# equalizer_schematic.net
KiCad netlist of a schematic drawn in EAGLE
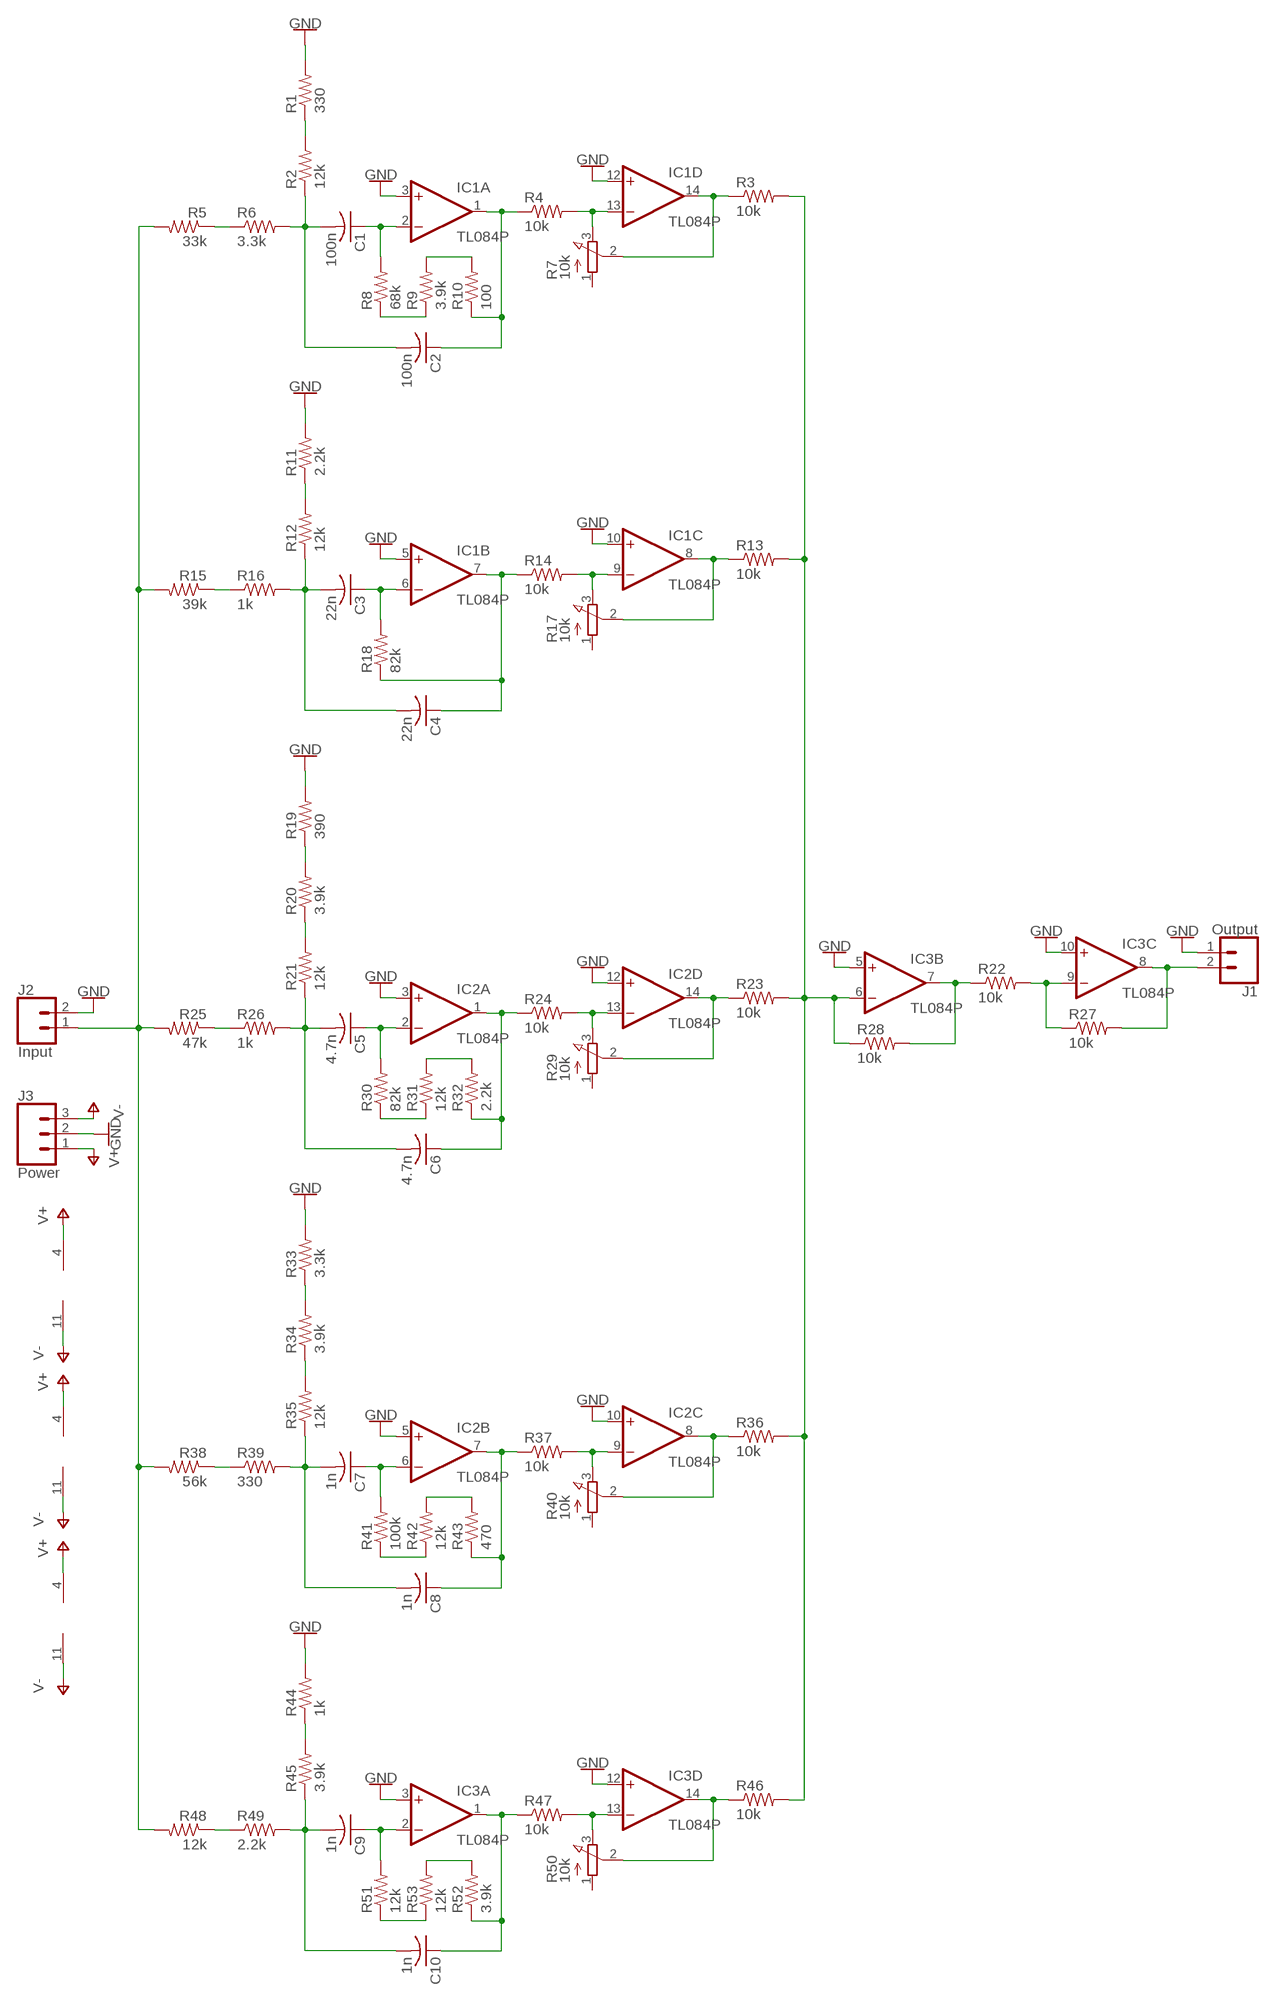
[diagram p0: schematic, sheet 1]

(export (version "E")
  (design (tool "Eeschema 10.0.6"))
  (components
    (comp (ref "C1")
      (value "100n")
      (footprint "eagle-import:C075-032X103")
      (libsource (lib "eagle-import") (part "C-US075-032X103"))
    )
    (comp (ref "C2")
      (value "100n")
      (footprint "eagle-import:C075-032X103")
      (libsource (lib "eagle-import") (part "C-US075-032X103"))
    )
    (comp (ref "C3")
      (value "22n")
      (footprint "eagle-import:C075-032X103")
      (libsource (lib "eagle-import") (part "C-US075-032X103"))
    )
    (comp (ref "C4")
      (value "22n")
      (footprint "eagle-import:C075-032X103")
      (libsource (lib "eagle-import") (part "C-US075-032X103"))
    )
    (comp (ref "C5")
      (value "4.7n")
      (footprint "eagle-import:C050-024X044")
      (libsource (lib "eagle-import") (part "C-US050-024X044"))
    )
    (comp (ref "C6")
      (value "4.7n")
      (footprint "eagle-import:C050-024X044")
      (libsource (lib "eagle-import") (part "C-US050-024X044"))
    )
    (comp (ref "C7")
      (value "1n")
      (footprint "eagle-import:C050-024X044")
      (libsource (lib "eagle-import") (part "C-US050-024X044"))
    )
    (comp (ref "C8")
      (value "1n")
      (footprint "eagle-import:C050-024X044")
      (libsource (lib "eagle-import") (part "C-US050-024X044"))
    )
    (comp (ref "C9")
      (value "1n")
      (footprint "eagle-import:C050-024X044")
      (libsource (lib "eagle-import") (part "C-US050-024X044"))
    )
    (comp (ref "C10")
      (value "1n")
      (footprint "eagle-import:C050-024X044")
      (libsource (lib "eagle-import") (part "C-US050-024X044"))
    )
    (comp (ref "IC1")
      (value "TL084P")
      (footprint "eagle-import:DIL14")
      (libsource (lib "eagle-import") (part "TL084P"))
    )
    (comp (ref "IC2")
      (value "TL084P")
      (footprint "eagle-import:DIL14")
      (libsource (lib "eagle-import") (part "TL084P"))
    )
    (comp (ref "IC3")
      (value "TL084P")
      (footprint "eagle-import:DIL14")
      (libsource (lib "eagle-import") (part "TL084P"))
    )
    (comp (ref "J1")
      (value "Output")
      (footprint "eagle-import:SCREWTERMINAL-5MM-2")
      (libsource (lib "eagle-import") (part "CONN_025MM"))
    )
    (comp (ref "J2")
      (value "Input")
      (footprint "eagle-import:SCREWTERMINAL-5MM-2")
      (libsource (lib "eagle-import") (part "CONN_025MM"))
    )
    (comp (ref "J3")
      (value "Power")
      (footprint "eagle-import:SCREWTERMINAL-5MM-3")
      (libsource (lib "eagle-import") (part "CONN_03-SCREW-5MM"))
    )
    (comp (ref "R1")
      (value "330")
      (footprint "eagle-import:0207_7")
      (libsource (lib "eagle-import") (part "R-US_0207/7"))
    )
    (comp (ref "R2")
      (value "12k")
      (footprint "eagle-import:0207_7")
      (libsource (lib "eagle-import") (part "R-US_0207/7"))
    )
    (comp (ref "R3")
      (value "10k")
      (footprint "eagle-import:0207_7")
      (libsource (lib "eagle-import") (part "R-US_0207/7"))
    )
    (comp (ref "R4")
      (value "10k")
      (footprint "eagle-import:0207_7")
      (libsource (lib "eagle-import") (part "R-US_0207/7"))
    )
    (comp (ref "R5")
      (value "33k")
      (footprint "eagle-import:0207_7")
      (libsource (lib "eagle-import") (part "R-US_0207/7"))
    )
    (comp (ref "R6")
      (value "3.3k")
      (footprint "eagle-import:0207_7")
      (libsource (lib "eagle-import") (part "R-US_0207/7"))
    )
    (comp (ref "R7")
      (value "10k")
      (footprint "eagle-import:3RP_1610N")
      (libsource (lib "eagle-import") (part "3RP/1610N"))
    )
    (comp (ref "R8")
      (value "68k")
      (footprint "eagle-import:0207_7")
      (libsource (lib "eagle-import") (part "R-US_0207/7"))
    )
    (comp (ref "R9")
      (value "3.9k")
      (footprint "eagle-import:0207_7")
      (libsource (lib "eagle-import") (part "R-US_0207/7"))
    )
    (comp (ref "R10")
      (value "100")
      (footprint "eagle-import:0207_7")
      (libsource (lib "eagle-import") (part "R-US_0207/7"))
    )
    (comp (ref "R11")
      (value "2.2k")
      (footprint "eagle-import:0207_7")
      (libsource (lib "eagle-import") (part "R-US_0207/7"))
    )
    (comp (ref "R12")
      (value "12k")
      (footprint "eagle-import:0207_7")
      (libsource (lib "eagle-import") (part "R-US_0207/7"))
    )
    (comp (ref "R13")
      (value "10k")
      (footprint "eagle-import:0207_7")
      (libsource (lib "eagle-import") (part "R-US_0207/7"))
    )
    (comp (ref "R14")
      (value "10k")
      (footprint "eagle-import:0207_7")
      (libsource (lib "eagle-import") (part "R-US_0207/7"))
    )
    (comp (ref "R15")
      (value "39k")
      (footprint "eagle-import:0207_7")
      (libsource (lib "eagle-import") (part "R-US_0207/7"))
    )
    (comp (ref "R16")
      (value "1k")
      (footprint "eagle-import:0207_7")
      (libsource (lib "eagle-import") (part "R-US_0207/7"))
    )
    (comp (ref "R17")
      (value "10k")
      (footprint "eagle-import:3RP_1610N")
      (libsource (lib "eagle-import") (part "3RP/1610N"))
    )
    (comp (ref "R18")
      (value "82k")
      (footprint "eagle-import:0207_7")
      (libsource (lib "eagle-import") (part "R-US_0207/7"))
    )
    (comp (ref "R19")
      (value "390")
      (footprint "eagle-import:0207_7")
      (libsource (lib "eagle-import") (part "R-US_0207/7"))
    )
    (comp (ref "R20")
      (value "3.9k")
      (footprint "eagle-import:0207_7")
      (libsource (lib "eagle-import") (part "R-US_0207/7"))
    )
    (comp (ref "R21")
      (value "12k")
      (footprint "eagle-import:0207_7")
      (libsource (lib "eagle-import") (part "R-US_0207/7"))
    )
    (comp (ref "R22")
      (value "10k")
      (footprint "eagle-import:0207_7")
      (libsource (lib "eagle-import") (part "R-US_0207/7"))
    )
    (comp (ref "R23")
      (value "10k")
      (footprint "eagle-import:0207_7")
      (libsource (lib "eagle-import") (part "R-US_0207/7"))
    )
    (comp (ref "R24")
      (value "10k")
      (footprint "eagle-import:0207_7")
      (libsource (lib "eagle-import") (part "R-US_0207/7"))
    )
    (comp (ref "R25")
      (value "47k")
      (footprint "eagle-import:0207_7")
      (libsource (lib "eagle-import") (part "R-US_0207/7"))
    )
    (comp (ref "R26")
      (value "1k")
      (footprint "eagle-import:0207_7")
      (libsource (lib "eagle-import") (part "R-US_0207/7"))
    )
    (comp (ref "R27")
      (value "10k")
      (footprint "eagle-import:0207_7")
      (libsource (lib "eagle-import") (part "R-US_0207/7"))
    )
    (comp (ref "R28")
      (value "10k")
      (footprint "eagle-import:0207_7")
      (libsource (lib "eagle-import") (part "R-US_0207/7"))
    )
    (comp (ref "R29")
      (value "10k")
      (footprint "eagle-import:3RP_1610N")
      (libsource (lib "eagle-import") (part "3RP/1610N"))
    )
    (comp (ref "R30")
      (value "82k")
      (footprint "eagle-import:0207_7")
      (libsource (lib "eagle-import") (part "R-US_0207/7"))
    )
    (comp (ref "R31")
      (value "12k")
      (footprint "eagle-import:0207_7")
      (libsource (lib "eagle-import") (part "R-US_0207/7"))
    )
    (comp (ref "R32")
      (value "2.2k")
      (footprint "eagle-import:0207_7")
      (libsource (lib "eagle-import") (part "R-US_0207/7"))
    )
    (comp (ref "R33")
      (value "3.3k")
      (footprint "eagle-import:0207_7")
      (libsource (lib "eagle-import") (part "R-US_0207/7"))
    )
    (comp (ref "R34")
      (value "3.9k")
      (footprint "eagle-import:0207_7")
      (libsource (lib "eagle-import") (part "R-US_0207/7"))
    )
    (comp (ref "R35")
      (value "12k")
      (footprint "eagle-import:0207_7")
      (libsource (lib "eagle-import") (part "R-US_0207/7"))
    )
    (comp (ref "R36")
      (value "10k")
      (footprint "eagle-import:0207_7")
      (libsource (lib "eagle-import") (part "R-US_0207/7"))
    )
    (comp (ref "R37")
      (value "10k")
      (footprint "eagle-import:0207_7")
      (libsource (lib "eagle-import") (part "R-US_0207/7"))
    )
    (comp (ref "R38")
      (value "56k")
      (footprint "eagle-import:0207_7")
      (libsource (lib "eagle-import") (part "R-US_0207/7"))
    )
    (comp (ref "R39")
      (value "330")
      (footprint "eagle-import:0207_7")
      (libsource (lib "eagle-import") (part "R-US_0207/7"))
    )
    (comp (ref "R40")
      (value "10k")
      (footprint "eagle-import:3RP_1610N")
      (libsource (lib "eagle-import") (part "3RP/1610N"))
    )
    (comp (ref "R41")
      (value "100k")
      (footprint "eagle-import:0207_7")
      (libsource (lib "eagle-import") (part "R-US_0207/7"))
    )
    (comp (ref "R42")
      (value "12k")
      (footprint "eagle-import:0207_7")
      (libsource (lib "eagle-import") (part "R-US_0207/7"))
    )
    (comp (ref "R43")
      (value "470")
      (footprint "eagle-import:0207_7")
      (libsource (lib "eagle-import") (part "R-US_0207/7"))
    )
    (comp (ref "R44")
      (value "1k")
      (footprint "eagle-import:0207_7")
      (libsource (lib "eagle-import") (part "R-US_0207/7"))
    )
    (comp (ref "R45")
      (value "3.9k")
      (footprint "eagle-import:0207_7")
      (libsource (lib "eagle-import") (part "R-US_0207/7"))
    )
    (comp (ref "R46")
      (value "10k")
      (footprint "eagle-import:0207_7")
      (libsource (lib "eagle-import") (part "R-US_0207/7"))
    )
    (comp (ref "R47")
      (value "10k")
      (footprint "eagle-import:0207_7")
      (libsource (lib "eagle-import") (part "R-US_0207/7"))
    )
    (comp (ref "R48")
      (value "12k")
      (footprint "eagle-import:0207_7")
      (libsource (lib "eagle-import") (part "R-US_0207/7"))
    )
    (comp (ref "R49")
      (value "2.2k")
      (footprint "eagle-import:0207_7")
      (libsource (lib "eagle-import") (part "R-US_0207/7"))
    )
    (comp (ref "R50")
      (value "10k")
      (footprint "eagle-import:3RP_1610N")
      (libsource (lib "eagle-import") (part "3RP/1610N"))
    )
    (comp (ref "R51")
      (value "12k")
      (footprint "eagle-import:0207_7")
      (libsource (lib "eagle-import") (part "R-US_0207/7"))
    )
    (comp (ref "R52")
      (value "3.9k")
      (footprint "eagle-import:0207_7")
      (libsource (lib "eagle-import") (part "R-US_0207/7"))
    )
    (comp (ref "R53")
      (value "12k")
      (footprint "eagle-import:0207_7")
      (libsource (lib "eagle-import") (part "R-US_0207/7"))
    )
  )
  (nets
    (net (code "1") (name "GND") (class "Default")
      (node (ref "IC1") (pin "10") (pinfunction "+IN_10") (pintype "input"))
      (node (ref "IC1") (pin "12") (pinfunction "+IN_12") (pintype "input"))
      (node (ref "IC1") (pin "3") (pinfunction "+IN_3") (pintype "input"))
      (node (ref "IC1") (pin "5") (pinfunction "+IN_5") (pintype "input"))
      (node (ref "IC2") (pin "10") (pinfunction "+IN_10") (pintype "input"))
      (node (ref "IC2") (pin "12") (pinfunction "+IN_12") (pintype "input"))
      (node (ref "IC2") (pin "3") (pinfunction "+IN_3") (pintype "input"))
      (node (ref "IC2") (pin "5") (pinfunction "+IN_5") (pintype "input"))
      (node (ref "IC3") (pin "10") (pinfunction "+IN_10") (pintype "input"))
      (node (ref "IC3") (pin "12") (pinfunction "+IN_12") (pintype "input"))
      (node (ref "IC3") (pin "3") (pinfunction "+IN_3") (pintype "input"))
      (node (ref "IC3") (pin "5") (pinfunction "+IN_5") (pintype "input"))
      (node (ref "J1") (pin "1") (pinfunction "1_1") (pintype "passive"))
      (node (ref "J2") (pin "2") (pinfunction "2_2") (pintype "passive"))
      (node (ref "J3") (pin "2") (pinfunction "2_2") (pintype "passive"))
      (node (ref "R1") (pin "2") (pinfunction "2_2") (pintype "passive"))
      (node (ref "R11") (pin "2") (pinfunction "2_2") (pintype "passive"))
      (node (ref "R19") (pin "2") (pinfunction "2_2") (pintype "passive"))
      (node (ref "R33") (pin "2") (pinfunction "2_2") (pintype "passive"))
      (node (ref "R44") (pin "2") (pinfunction "2_2") (pintype "passive"))
    )
    (net (code "2") (name "Net-(C1-Pad2)") (class "Default")
      (node (ref "C1") (pin "2") (pinfunction "2_2") (pintype "passive"))
      (node (ref "C2") (pin "2") (pinfunction "2_2") (pintype "passive"))
      (node (ref "R2") (pin "1") (pinfunction "1_1") (pintype "passive"))
      (node (ref "R6") (pin "2") (pinfunction "2_2") (pintype "passive"))
    )
    (net (code "3") (name "Net-(C3-Pad2)") (class "Default")
      (node (ref "C3") (pin "2") (pinfunction "2_2") (pintype "passive"))
      (node (ref "C4") (pin "2") (pinfunction "2_2") (pintype "passive"))
      (node (ref "R12") (pin "1") (pinfunction "1_1") (pintype "passive"))
      (node (ref "R16") (pin "2") (pinfunction "2_2") (pintype "passive"))
    )
    (net (code "4") (name "Net-(C5-Pad2)") (class "Default")
      (node (ref "C5") (pin "2") (pinfunction "2_2") (pintype "passive"))
      (node (ref "C6") (pin "2") (pinfunction "2_2") (pintype "passive"))
      (node (ref "R21") (pin "1") (pinfunction "1_1") (pintype "passive"))
      (node (ref "R26") (pin "2") (pinfunction "2_2") (pintype "passive"))
    )
    (net (code "5") (name "Net-(C7-Pad2)") (class "Default")
      (node (ref "C7") (pin "2") (pinfunction "2_2") (pintype "passive"))
      (node (ref "C8") (pin "2") (pinfunction "2_2") (pintype "passive"))
      (node (ref "R35") (pin "1") (pinfunction "1_1") (pintype "passive"))
      (node (ref "R39") (pin "2") (pinfunction "2_2") (pintype "passive"))
    )
    (net (code "6") (name "Net-(C10-Pad2)") (class "Default")
      (node (ref "C10") (pin "2") (pinfunction "2_2") (pintype "passive"))
      (node (ref "C9") (pin "2") (pinfunction "2_2") (pintype "passive"))
      (node (ref "R45") (pin "1") (pinfunction "1_1") (pintype "passive"))
      (node (ref "R49") (pin "2") (pinfunction "2_2") (pintype "passive"))
    )
    (net (code "7") (name "Net-(IC1A--IN)") (class "Default")
      (node (ref "C1") (pin "1") (pinfunction "1_1") (pintype "passive"))
      (node (ref "IC1") (pin "2") (pinfunction "-IN_2") (pintype "input"))
      (node (ref "R8") (pin "2") (pinfunction "2_2") (pintype "passive"))
    )
    (net (code "8") (name "Net-(IC1A-OUT)") (class "Default")
      (node (ref "C2") (pin "1") (pinfunction "1_1") (pintype "passive"))
      (node (ref "IC1") (pin "1") (pinfunction "OUT_1") (pintype "output"))
      (node (ref "R10") (pin "1") (pinfunction "1_1") (pintype "passive"))
      (node (ref "R4") (pin "1") (pinfunction "1_1") (pintype "passive"))
    )
    (net (code "9") (name "Net-(IC1B--IN)") (class "Default")
      (node (ref "C3") (pin "1") (pinfunction "1_1") (pintype "passive"))
      (node (ref "IC1") (pin "6") (pinfunction "-IN_6") (pintype "input"))
      (node (ref "R18") (pin "2") (pinfunction "2_2") (pintype "passive"))
    )
    (net (code "10") (name "Net-(IC1B-OUT)") (class "Default")
      (node (ref "C4") (pin "1") (pinfunction "1_1") (pintype "passive"))
      (node (ref "IC1") (pin "7") (pinfunction "OUT_7") (pintype "output"))
      (node (ref "R14") (pin "1") (pinfunction "1_1") (pintype "passive"))
      (node (ref "R18") (pin "1") (pinfunction "1_1") (pintype "passive"))
    )
    (net (code "11") (name "Net-(IC1C--IN)") (class "Default")
      (node (ref "IC1") (pin "9") (pinfunction "-IN_9") (pintype "input"))
      (node (ref "R14") (pin "2") (pinfunction "2_2") (pintype "passive"))
      (node (ref "R17") (pin "3") (pinfunction "E_3") (pintype "passive"))
    )
    (net (code "12") (name "Net-(IC1C-OUT)") (class "Default")
      (node (ref "IC1") (pin "8") (pinfunction "OUT_8") (pintype "output"))
      (node (ref "R13") (pin "1") (pinfunction "1_1") (pintype "passive"))
      (node (ref "R17") (pin "2") (pinfunction "S_2") (pintype "passive"))
    )
    (net (code "13") (name "Net-(IC1D--IN)") (class "Default")
      (node (ref "IC1") (pin "13") (pinfunction "-IN_13") (pintype "input"))
      (node (ref "R4") (pin "2") (pinfunction "2_2") (pintype "passive"))
      (node (ref "R7") (pin "3") (pinfunction "E_3") (pintype "passive"))
    )
    (net (code "14") (name "Net-(IC1D-OUT)") (class "Default")
      (node (ref "IC1") (pin "14") (pinfunction "OUT_14") (pintype "output"))
      (node (ref "R3") (pin "1") (pinfunction "1_1") (pintype "passive"))
      (node (ref "R7") (pin "2") (pinfunction "S_2") (pintype "passive"))
    )
    (net (code "15") (name "Net-(IC2A--IN)") (class "Default")
      (node (ref "C5") (pin "1") (pinfunction "1_1") (pintype "passive"))
      (node (ref "IC2") (pin "2") (pinfunction "-IN_2") (pintype "input"))
      (node (ref "R30") (pin "2") (pinfunction "2_2") (pintype "passive"))
    )
    (net (code "16") (name "Net-(IC2A-OUT)") (class "Default")
      (node (ref "C6") (pin "1") (pinfunction "1_1") (pintype "passive"))
      (node (ref "IC2") (pin "1") (pinfunction "OUT_1") (pintype "output"))
      (node (ref "R24") (pin "1") (pinfunction "1_1") (pintype "passive"))
      (node (ref "R32") (pin "1") (pinfunction "1_1") (pintype "passive"))
    )
    (net (code "17") (name "Net-(IC2B--IN)") (class "Default")
      (node (ref "C7") (pin "1") (pinfunction "1_1") (pintype "passive"))
      (node (ref "IC2") (pin "6") (pinfunction "-IN_6") (pintype "input"))
      (node (ref "R41") (pin "2") (pinfunction "2_2") (pintype "passive"))
    )
    (net (code "18") (name "Net-(IC2B-OUT)") (class "Default")
      (node (ref "C8") (pin "1") (pinfunction "1_1") (pintype "passive"))
      (node (ref "IC2") (pin "7") (pinfunction "OUT_7") (pintype "output"))
      (node (ref "R37") (pin "1") (pinfunction "1_1") (pintype "passive"))
      (node (ref "R43") (pin "1") (pinfunction "1_1") (pintype "passive"))
    )
    (net (code "19") (name "Net-(IC2C--IN)") (class "Default")
      (node (ref "IC2") (pin "9") (pinfunction "-IN_9") (pintype "input"))
      (node (ref "R37") (pin "2") (pinfunction "2_2") (pintype "passive"))
      (node (ref "R40") (pin "3") (pinfunction "E_3") (pintype "passive"))
    )
    (net (code "20") (name "Net-(IC2C-OUT)") (class "Default")
      (node (ref "IC2") (pin "8") (pinfunction "OUT_8") (pintype "output"))
      (node (ref "R36") (pin "1") (pinfunction "1_1") (pintype "passive"))
      (node (ref "R40") (pin "2") (pinfunction "S_2") (pintype "passive"))
    )
    (net (code "21") (name "Net-(IC2D--IN)") (class "Default")
      (node (ref "IC2") (pin "13") (pinfunction "-IN_13") (pintype "input"))
      (node (ref "R24") (pin "2") (pinfunction "2_2") (pintype "passive"))
      (node (ref "R29") (pin "3") (pinfunction "E_3") (pintype "passive"))
    )
    (net (code "22") (name "Net-(IC2D-OUT)") (class "Default")
      (node (ref "IC2") (pin "14") (pinfunction "OUT_14") (pintype "output"))
      (node (ref "R23") (pin "1") (pinfunction "1_1") (pintype "passive"))
      (node (ref "R29") (pin "2") (pinfunction "S_2") (pintype "passive"))
    )
    (net (code "23") (name "Net-(IC3A--IN)") (class "Default")
      (node (ref "C9") (pin "1") (pinfunction "1_1") (pintype "passive"))
      (node (ref "IC3") (pin "2") (pinfunction "-IN_2") (pintype "input"))
      (node (ref "R51") (pin "2") (pinfunction "2_2") (pintype "passive"))
    )
    (net (code "24") (name "Net-(IC3A-OUT)") (class "Default")
      (node (ref "C10") (pin "1") (pinfunction "1_1") (pintype "passive"))
      (node (ref "IC3") (pin "1") (pinfunction "OUT_1") (pintype "output"))
      (node (ref "R47") (pin "1") (pinfunction "1_1") (pintype "passive"))
      (node (ref "R52") (pin "1") (pinfunction "1_1") (pintype "passive"))
    )
    (net (code "25") (name "Net-(IC3B--IN)") (class "Default")
      (node (ref "IC3") (pin "6") (pinfunction "-IN_6") (pintype "input"))
      (node (ref "R13") (pin "2") (pinfunction "2_2") (pintype "passive"))
      (node (ref "R23") (pin "2") (pinfunction "2_2") (pintype "passive"))
      (node (ref "R28") (pin "1") (pinfunction "1_1") (pintype "passive"))
      (node (ref "R3") (pin "2") (pinfunction "2_2") (pintype "passive"))
      (node (ref "R36") (pin "2") (pinfunction "2_2") (pintype "passive"))
      (node (ref "R46") (pin "2") (pinfunction "2_2") (pintype "passive"))
    )
    (net (code "26") (name "Net-(IC3B-OUT)") (class "Default")
      (node (ref "IC3") (pin "7") (pinfunction "OUT_7") (pintype "output"))
      (node (ref "R22") (pin "1") (pinfunction "1_1") (pintype "passive"))
      (node (ref "R28") (pin "2") (pinfunction "2_2") (pintype "passive"))
    )
    (net (code "27") (name "Net-(IC3C--IN)") (class "Default")
      (node (ref "IC3") (pin "9") (pinfunction "-IN_9") (pintype "input"))
      (node (ref "R22") (pin "2") (pinfunction "2_2") (pintype "passive"))
      (node (ref "R27") (pin "1") (pinfunction "1_1") (pintype "passive"))
    )
    (net (code "28") (name "Net-(IC3C-OUT)") (class "Default")
      (node (ref "IC3") (pin "8") (pinfunction "OUT_8") (pintype "output"))
      (node (ref "J1") (pin "2") (pinfunction "2_2") (pintype "passive"))
      (node (ref "R27") (pin "2") (pinfunction "2_2") (pintype "passive"))
    )
    (net (code "29") (name "Net-(IC3D--IN)") (class "Default")
      (node (ref "IC3") (pin "13") (pinfunction "-IN_13") (pintype "input"))
      (node (ref "R47") (pin "2") (pinfunction "2_2") (pintype "passive"))
      (node (ref "R50") (pin "3") (pinfunction "E_3") (pintype "passive"))
    )
    (net (code "30") (name "Net-(IC3D-OUT)") (class "Default")
      (node (ref "IC3") (pin "14") (pinfunction "OUT_14") (pintype "output"))
      (node (ref "R46") (pin "1") (pinfunction "1_1") (pintype "passive"))
      (node (ref "R50") (pin "2") (pinfunction "S_2") (pintype "passive"))
    )
    (net (code "31") (name "Net-(J2-Pad1)") (class "Default")
      (node (ref "J2") (pin "1") (pinfunction "1_1") (pintype "passive"))
      (node (ref "R15") (pin "2") (pinfunction "2_2") (pintype "passive"))
      (node (ref "R25") (pin "2") (pinfunction "2_2") (pintype "passive"))
      (node (ref "R38") (pin "2") (pinfunction "2_2") (pintype "passive"))
      (node (ref "R48") (pin "2") (pinfunction "2_2") (pintype "passive"))
      (node (ref "R5") (pin "2") (pinfunction "2_2") (pintype "passive"))
    )
    (net (code "32") (name "Net-(R1-Pad1)") (class "Default")
      (node (ref "R1") (pin "1") (pinfunction "1_1") (pintype "passive"))
      (node (ref "R2") (pin "2") (pinfunction "2_2") (pintype "passive"))
    )
    (net (code "33") (name "Net-(R5-Pad1)") (class "Default")
      (node (ref "R5") (pin "1") (pinfunction "1_1") (pintype "passive"))
      (node (ref "R6") (pin "1") (pinfunction "1_1") (pintype "passive"))
    )
    (net (code "34") (name "Net-(R8-Pad1)") (class "Default")
      (node (ref "R8") (pin "1") (pinfunction "1_1") (pintype "passive"))
      (node (ref "R9") (pin "1") (pinfunction "1_1") (pintype "passive"))
    )
    (net (code "35") (name "Net-(R10-Pad2)") (class "Default")
      (node (ref "R10") (pin "2") (pinfunction "2_2") (pintype "passive"))
      (node (ref "R9") (pin "2") (pinfunction "2_2") (pintype "passive"))
    )
    (net (code "36") (name "Net-(R11-Pad1)") (class "Default")
      (node (ref "R11") (pin "1") (pinfunction "1_1") (pintype "passive"))
      (node (ref "R12") (pin "2") (pinfunction "2_2") (pintype "passive"))
    )
    (net (code "37") (name "Net-(R15-Pad1)") (class "Default")
      (node (ref "R15") (pin "1") (pinfunction "1_1") (pintype "passive"))
      (node (ref "R16") (pin "1") (pinfunction "1_1") (pintype "passive"))
    )
    (net (code "38") (name "Net-(R19-Pad1)") (class "Default")
      (node (ref "R19") (pin "1") (pinfunction "1_1") (pintype "passive"))
      (node (ref "R20") (pin "2") (pinfunction "2_2") (pintype "passive"))
    )
    (net (code "39") (name "Net-(R20-Pad1)") (class "Default")
      (node (ref "R20") (pin "1") (pinfunction "1_1") (pintype "passive"))
      (node (ref "R21") (pin "2") (pinfunction "2_2") (pintype "passive"))
    )
    (net (code "40") (name "Net-(R25-Pad1)") (class "Default")
      (node (ref "R25") (pin "1") (pinfunction "1_1") (pintype "passive"))
      (node (ref "R26") (pin "1") (pinfunction "1_1") (pintype "passive"))
    )
    (net (code "41") (name "Net-(R30-Pad1)") (class "Default")
      (node (ref "R30") (pin "1") (pinfunction "1_1") (pintype "passive"))
      (node (ref "R31") (pin "1") (pinfunction "1_1") (pintype "passive"))
    )
    (net (code "42") (name "Net-(R31-Pad2)") (class "Default")
      (node (ref "R31") (pin "2") (pinfunction "2_2") (pintype "passive"))
      (node (ref "R32") (pin "2") (pinfunction "2_2") (pintype "passive"))
    )
    (net (code "43") (name "Net-(R33-Pad1)") (class "Default")
      (node (ref "R33") (pin "1") (pinfunction "1_1") (pintype "passive"))
      (node (ref "R34") (pin "2") (pinfunction "2_2") (pintype "passive"))
    )
    (net (code "44") (name "Net-(R34-Pad1)") (class "Default")
      (node (ref "R34") (pin "1") (pinfunction "1_1") (pintype "passive"))
      (node (ref "R35") (pin "2") (pinfunction "2_2") (pintype "passive"))
    )
    (net (code "45") (name "Net-(R38-Pad1)") (class "Default")
      (node (ref "R38") (pin "1") (pinfunction "1_1") (pintype "passive"))
      (node (ref "R39") (pin "1") (pinfunction "1_1") (pintype "passive"))
    )
    (net (code "46") (name "Net-(R41-Pad1)") (class "Default")
      (node (ref "R41") (pin "1") (pinfunction "1_1") (pintype "passive"))
      (node (ref "R42") (pin "1") (pinfunction "1_1") (pintype "passive"))
    )
    (net (code "47") (name "Net-(R42-Pad2)") (class "Default")
      (node (ref "R42") (pin "2") (pinfunction "2_2") (pintype "passive"))
      (node (ref "R43") (pin "2") (pinfunction "2_2") (pintype "passive"))
    )
    (net (code "48") (name "Net-(R44-Pad1)") (class "Default")
      (node (ref "R44") (pin "1") (pinfunction "1_1") (pintype "passive"))
      (node (ref "R45") (pin "2") (pinfunction "2_2") (pintype "passive"))
    )
    (net (code "49") (name "Net-(R48-Pad1)") (class "Default")
      (node (ref "R48") (pin "1") (pinfunction "1_1") (pintype "passive"))
      (node (ref "R49") (pin "1") (pinfunction "1_1") (pintype "passive"))
    )
    (net (code "50") (name "Net-(R51-Pad1)") (class "Default")
      (node (ref "R51") (pin "1") (pinfunction "1_1") (pintype "passive"))
      (node (ref "R53") (pin "1") (pinfunction "1_1") (pintype "passive"))
    )
    (net (code "51") (name "Net-(R52-Pad2)") (class "Default")
      (node (ref "R52") (pin "2") (pinfunction "2_2") (pintype "passive"))
      (node (ref "R53") (pin "2") (pinfunction "2_2") (pintype "passive"))
    )
    (net (code "52") (name "V+") (class "Default")
      (node (ref "IC1") (pin "4") (pinfunction "V+_4") (pintype "power_in"))
      (node (ref "IC2") (pin "4") (pinfunction "V+_4") (pintype "power_in"))
      (node (ref "IC3") (pin "4") (pinfunction "V+_4") (pintype "power_in"))
      (node (ref "J3") (pin "1") (pinfunction "1_1") (pintype "passive"))
    )
    (net (code "53") (name "V-") (class "Default")
      (node (ref "IC1") (pin "11") (pinfunction "V-_11") (pintype "power_in"))
      (node (ref "IC2") (pin "11") (pinfunction "V-_11") (pintype "power_in"))
      (node (ref "IC3") (pin "11") (pinfunction "V-_11") (pintype "power_in"))
      (node (ref "J3") (pin "3") (pinfunction "3_3") (pintype "passive"))
    )
    (net (code "54") (name "unconnected-(R7-A-Pad1)") (class "Default")
      (node (ref "R7") (pin "1") (pinfunction "A_1") (pintype "passive"))
    )
    (net (code "55") (name "unconnected-(R17-A-Pad1)") (class "Default")
      (node (ref "R17") (pin "1") (pinfunction "A_1") (pintype "passive"))
    )
    (net (code "56") (name "unconnected-(R29-A-Pad1)") (class "Default")
      (node (ref "R29") (pin "1") (pinfunction "A_1") (pintype "passive"))
    )
    (net (code "57") (name "unconnected-(R40-A-Pad1)") (class "Default")
      (node (ref "R40") (pin "1") (pinfunction "A_1") (pintype "passive"))
    )
    (net (code "58") (name "unconnected-(R50-A-Pad1)") (class "Default")
      (node (ref "R50") (pin "1") (pinfunction "A_1") (pintype "passive"))
    )
  )
)
